# PROC099A_XDS110_Interface_1B.net
KiCad netlist of a schematic drawn in Altium Designer
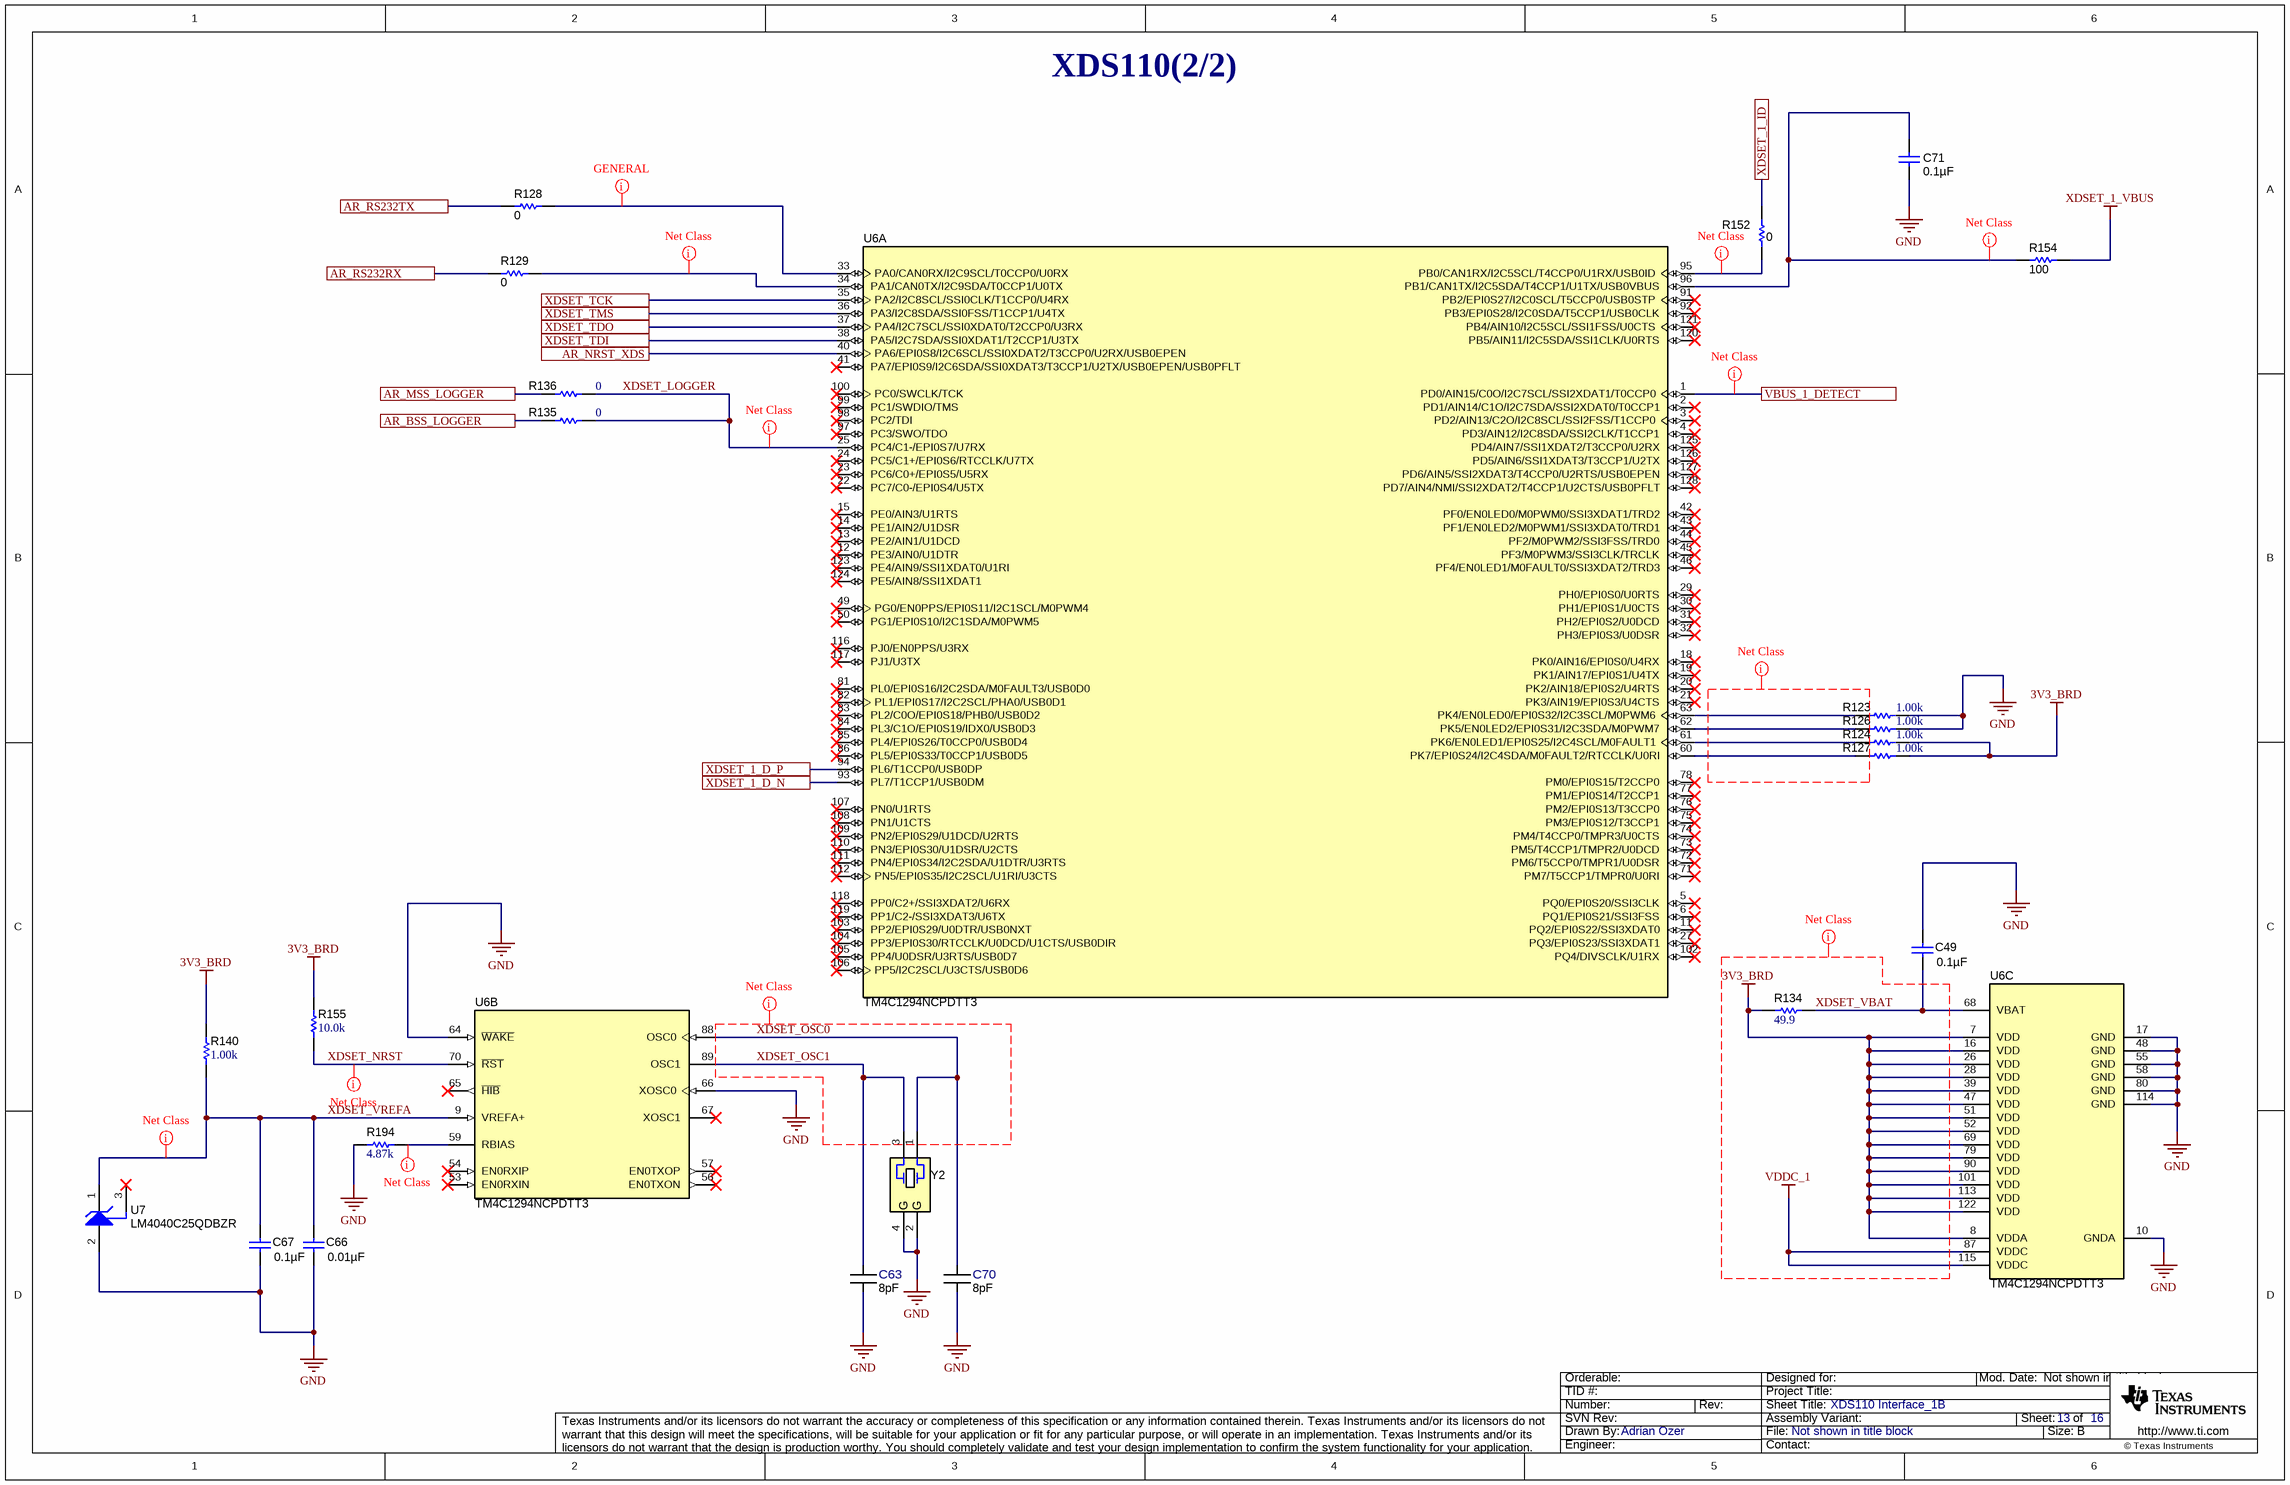
[diagram p0: PROC099A_XDS110 Interface_1B.SchDoc]

(export (version "E")
  (design (tool "Eeschema 10.0.6"))
  (components
    (comp (ref "C49")
      (value "C0402C104K8RACTU")
      (footprint "0402L")
      (description "CAP, CERM, 0.1 µF, 10 V,+/- 10%, X7R, 0402")
      (fields (field (name "MANUFACTURER") "Kemet") (field (name "VALUEDISPLAYED") "0.1µF"))
      (libsource (lib "Altium Vault - TI") (part "CMP-0078241-1"))
    )
    (comp (ref "C63")
      (value "GCM1555C1H8R0DA16D")
      (footprint "FP-GCM1555C1H8R0DA16_0402-MFG")
      (description "Cap Ceramic 8pF 50V C0G 0.5pF SMD 0402 125C Paper T/R")
      (fields (field (name "CAP_F") "8pF") (field (name "MANUFACTURER") "Murata Electronics North America"))
      (libsource (lib "Altium Vault - TI") (part "SYM-B32642B0223J"))
    )
    (comp (ref "C66")
      (value "C0402C103K4RACTU")
      (footprint "0402L")
      (description "CAP, CERM, 0.01 µF, 16 V,+/- 10%, X7R, 0402")
      (fields (field (name "MANUFACTURER") "Kemet") (field (name "VALUEDISPLAYED") "0.01µF"))
      (libsource (lib "Altium Vault - TI") (part "Capacitor"))
    )
    (comp (ref "C67")
      (value "C0402C104K8RACTU")
      (footprint "0402L")
      (description "CAP, CERM, 0.1 µF, 10 V,+/- 10%, X7R, 0402")
      (fields (field (name "MANUFACTURER") "Kemet") (field (name "VALUEDISPLAYED") "0.1µF"))
      (libsource (lib "Altium Vault - TI") (part "Capacitor"))
    )
    (comp (ref "C70")
      (value "GCM1555C1H8R0DA16D")
      (footprint "FP-GCM1555C1H8R0DA16_0402-MFG")
      (description "Cap Ceramic 8pF 50V C0G 0.5pF SMD 0402 125C Paper T/R")
      (fields (field (name "CAP_F") "8pF") (field (name "MANUFACTURER") "Murata Electronics North America"))
      (libsource (lib "Altium Vault - TI") (part "SYM-B32642B0223J"))
    )
    (comp (ref "C71")
      (value "C0402C104K8RACTU")
      (footprint "0402L")
      (description "CAP, CERM, 0.1 µF, 10 V,+/- 10%, X7R, 0402")
      (fields (field (name "MANUFACTURER") "Kemet") (field (name "VALUEDISPLAYED") "0.1µF"))
      (libsource (lib "Altium Vault - TI") (part "Capacitor"))
    )
    (comp (ref "R123")
      (value "CRCW04021K00FKED")
      (footprint "0402L")
      (description "RES, 1.00 k, 1%, 0.063 W, AEC-Q200 Grade 0, 0402")
      (fields (field (name "MANUFACTURER") "Vishay-Dale") (field (name "VALUEDISPLAYED") "1.00k"))
      (libsource (lib "Altium Vault - TI") (part "Resistor"))
    )
    (comp (ref "R124")
      (value "CRCW04021K00FKED")
      (footprint "0402L")
      (description "RES, 1.00 k, 1%, 0.063 W, AEC-Q200 Grade 0, 0402")
      (fields (field (name "MANUFACTURER") "Vishay-Dale") (field (name "VALUEDISPLAYED") "1.00k"))
      (libsource (lib "Altium Vault - TI") (part "Resistor"))
    )
    (comp (ref "R126")
      (value "CRCW04021K00FKED")
      (footprint "0402L")
      (description "RES, 1.00 k, 1%, 0.063 W, AEC-Q200 Grade 0, 0402")
      (fields (field (name "MANUFACTURER") "Vishay-Dale") (field (name "VALUEDISPLAYED") "1.00k"))
      (libsource (lib "Altium Vault - TI") (part "Resistor"))
    )
    (comp (ref "R127")
      (value "CRCW04021K00FKED")
      (footprint "0402L")
      (description "RES, 1.00 k, 1%, 0.063 W, AEC-Q200 Grade 0, 0402")
      (fields (field (name "MANUFACTURER") "Vishay-Dale") (field (name "VALUEDISPLAYED") "1.00k"))
      (libsource (lib "Altium Vault - TI") (part "Resistor"))
    )
    (comp (ref "R128")
      (value "ERJ-2GE0R00X")
      (footprint "0402L")
      (description "RES, 0, 5%, 0.063 W, 0402")
      (fields
        (field (name "MANUFACTURER") "Panasonic")
        (field (name "VALUEDISPLAYED") "0")
        (field (name "PUBLISHER") "Texas Instruments")
      )
      (libsource (lib "Altium Vault - TI") (part "Resistor"))
    )
    (comp (ref "R129")
      (value "ERJ-2GE0R00X")
      (footprint "0402L")
      (description "RES, 0, 5%, 0.063 W, 0402")
      (fields
        (field (name "MANUFACTURER") "Panasonic")
        (field (name "VALUEDISPLAYED") "0")
        (field (name "PUBLISHER") "Texas Instruments")
      )
      (libsource (lib "Altium Vault - TI") (part "Resistor"))
    )
    (comp (ref "R134")
      (value "CRCW040249R9FKED")
      (footprint "0402L")
      (description "RES, 49.9, 1%, 0.063 W, AEC-Q200 Grade 0, 0402")
      (fields (field (name "MANUFACTURER") "Vishay-Dale") (field (name "VALUEDISPLAYED") "49.9"))
      (libsource (lib "Altium Vault - TI") (part "Resistor"))
    )
    (comp (ref "R135")
      (value "CRCW02010000Z0ED")
      (footprint "0201_Silk")
      (description "RES, 0, 5%, 0.05 W, 0201")
      (fields (field (name "MANUFACTURER") "Vishay-Dale") (field (name "VALUEDISPLAYED") "0"))
      (libsource (lib "Altium Vault - TI") (part "Resistor"))
    )
    (comp (ref "R136")
      (value "CRCW02010000Z0ED")
      (footprint "0201_Silk")
      (description "RES, 0, 5%, 0.05 W, 0201")
      (fields (field (name "MANUFACTURER") "Vishay-Dale") (field (name "VALUEDISPLAYED") "0"))
      (libsource (lib "Altium Vault - TI") (part "Resistor"))
    )
    (comp (ref "R140")
      (value "CRCW04021K00FKED")
      (footprint "0402L")
      (description "RES, 1.00 k, 1%, 0.063 W, AEC-Q200 Grade 0, 0402")
      (fields (field (name "MANUFACTURER") "Vishay-Dale") (field (name "VALUEDISPLAYED") "1.00k"))
      (libsource (lib "Altium Vault - TI") (part "Resistor"))
    )
    (comp (ref "R152")
      (value "ERJ-2GE0R00X")
      (footprint "0402L")
      (description "RES, 0, 5%, 0.063 W, 0402")
      (fields
        (field (name "MANUFACTURER") "Panasonic")
        (field (name "VALUEDISPLAYED") "0")
        (field (name "PUBLISHER") "Texas Instruments")
      )
      (libsource (lib "Altium Vault - TI") (part "Resistor"))
    )
    (comp (ref "R154")
      (value "ERJ-2GEJ101X")
      (footprint "0402L")
      (description "RES, 100, 5%, 0.1 W, AEC-Q200 Grade 0, 0402")
      (fields
        (field (name "MANUFACTURER") "Panasonic")
        (field (name "VALUEDISPLAYED") "100")
        (field (name "PUBLISHER") "Texas Instruments")
      )
      (libsource (lib "Altium Vault - TI") (part "Resistor"))
    )
    (comp (ref "R155")
      (value "CRCW040210K0FKED")
      (footprint "0402L")
      (description "RES, 10.0 k, 1%, 0.063 W, AEC-Q200 Grade 0, 0402")
      (fields (field (name "MANUFACTURER") "Vishay-Dale") (field (name "VALUEDISPLAYED") "10.0k"))
      (libsource (lib "Altium Vault - TI") (part "Resistor"))
    )
    (comp (ref "R194")
      (value "CRCW04024K87FKED")
      (footprint "0402L")
      (description "RES, 4.87 k, 1%, 0.063 W, AEC-Q200 Grade 0, 0402")
      (fields (field (name "MANUFACTURER") "Vishay-Dale") (field (name "VALUEDISPLAYED") "4.87k"))
      (libsource (lib "Altium Vault - TI") (part "Resistor"))
    )
    (comp (ref "U6")
      (value "TM4C1294NCPDTT3")
      (footprint "PDT0128A")
      (fields (field (name "PARTNUMBER") "TM4C1294NCPDTT3") (field (name "MANUFACTURER") "Texas Instruments"))
      (libsource (lib "Altium Vault - TI") (part "TI-TM4C1294NCPDT-128"))
    )
    (comp (ref "U7")
      (value "LM4040C25QDBZR")
      (footprint "DBZ0003A_N")
      (fields (field (name "MANUFACTURER") "Texas Instruments") (field (name "PARTNUMBER") "LM4040C25QDBZR"))
      (libsource (lib "Altium Vault - TI") (part "TI-LM4040C25DBZ3"))
    )
    (comp (ref "Y2")
      (value "NX3225SA-16.000M-STD-CRS-2")
      (footprint "NDK_NX3225SA")
      (description "Crystal, 16 MHz, 15 ppm, 8 pF, AEC-Q200 Grade 1, SMD")
      (fields (field (name "MANUFACTURER") "NDK"))
      (libsource (lib "Altium Vault - TI") (part "CMP-0078214-2"))
    )
  )
  (nets
    (net (code "1") (name "/AR_BSS_LOGGER") (class "Default")
      (node (ref "R135") (pin "1") (pinfunction "1_1") (pintype "passive"))
    )
    (net (code "2") (name "/AR_MSS_LOGGER") (class "Default")
      (node (ref "R136") (pin "1") (pinfunction "1_1") (pintype "passive"))
    )
    (net (code "3") (name "/AR_NRST_XDS") (class "Default")
      (node (ref "U6") (pin "40") (pinfunction "PA6/EPI0S8/I2C6SCL/SSI0XDAT2/T3CCP0/U2RX/USB0EPEN_40") (pintype "bidirectional"))
    )
    (net (code "4") (name "/AR_RS232RX") (class "Default")
      (node (ref "R129") (pin "1") (pinfunction "1_1") (pintype "passive"))
    )
    (net (code "5") (name "/AR_RS232TX") (class "Default")
      (node (ref "R128") (pin "1") (pinfunction "1_1") (pintype "passive"))
    )
    (net (code "6") (name "/VBUS_1_DETECT") (class "Default")
      (node (ref "U6") (pin "1") (pinfunction "PD0/AIN15/C0O/I2C7SCL/SSI2XDAT1/T0CCP0_1") (pintype "bidirectional"))
    )
    (net (code "7") (name "/XDSET_1_D_N") (class "Default")
      (node (ref "U6") (pin "93") (pinfunction "PL7/T1CCP1/USB0DM_93") (pintype "bidirectional"))
    )
    (net (code "8") (name "/XDSET_1_D_P") (class "Default")
      (node (ref "U6") (pin "94") (pinfunction "PL6/T1CCP0/USB0DP_94") (pintype "bidirectional"))
    )
    (net (code "9") (name "/XDSET_1_ID") (class "Default")
      (node (ref "R152") (pin "2") (pinfunction "2_2") (pintype "passive"))
    )
    (net (code "10") (name "/XDSET_LOGGER") (class "Default")
      (node (ref "R135") (pin "2") (pinfunction "2_2") (pintype "passive"))
      (node (ref "R136") (pin "2") (pinfunction "2_2") (pintype "passive"))
      (node (ref "U6") (pin "25") (pinfunction "PC4/C1-/EPI0S7/U7RX_25") (pintype "bidirectional"))
    )
    (net (code "11") (name "/XDSET_NRST") (class "Default")
      (node (ref "R155") (pin "1") (pinfunction "1_1") (pintype "passive"))
      (node (ref "U6") (pin "70") (pinfunction "~{RST}_70") (pintype "input"))
    )
    (net (code "12") (name "/XDSET_OSC0") (class "Default")
      (node (ref "C70") (pin "1") (pinfunction "1_1") (pintype "passive"))
      (node (ref "U6") (pin "88") (pinfunction "OSC0_88") (pintype "input"))
      (node (ref "Y2") (pin "1") (pinfunction "1_1") (pintype "passive"))
    )
    (net (code "13") (name "/XDSET_OSC1") (class "Default")
      (node (ref "C63") (pin "1") (pinfunction "1_1") (pintype "passive"))
      (node (ref "U6") (pin "89") (pinfunction "OSC1_89") (pintype "passive"))
      (node (ref "Y2") (pin "3") (pinfunction "3_3") (pintype "passive"))
    )
    (net (code "14") (name "/XDSET_TCK") (class "Default")
      (node (ref "U6") (pin "35") (pinfunction "PA2/I2C8SCL/SSI0CLK/T1CCP0/U4RX_35") (pintype "bidirectional"))
    )
    (net (code "15") (name "/XDSET_TDI") (class "Default")
      (node (ref "U6") (pin "38") (pinfunction "PA5/I2C7SDA/SSI0XDAT1/T2CCP1/U3TX_38") (pintype "bidirectional"))
    )
    (net (code "16") (name "/XDSET_TDO") (class "Default")
      (node (ref "U6") (pin "37") (pinfunction "PA4/I2C7SCL/SSI0XDAT0/T2CCP0/U3RX_37") (pintype "bidirectional"))
    )
    (net (code "17") (name "/XDSET_TMS") (class "Default")
      (node (ref "U6") (pin "36") (pinfunction "PA3/I2C8SDA/SSI0FSS/T1CCP1/U4TX_36") (pintype "bidirectional"))
    )
    (net (code "18") (name "/XDSET_VBAT") (class "Default")
      (node (ref "C49") (pin "2") (pinfunction "2_2") (pintype "passive"))
      (node (ref "R134") (pin "1") (pinfunction "1_1") (pintype "passive"))
      (node (ref "U6") (pin "68") (pinfunction "VBAT_68") (pintype "power_in"))
    )
    (net (code "19") (name "/XDSET_VREFA") (class "Default")
      (node (ref "C66") (pin "2") (pinfunction "2_2") (pintype "passive"))
      (node (ref "C67") (pin "2") (pinfunction "2_2") (pintype "passive"))
      (node (ref "R140") (pin "1") (pinfunction "1_1") (pintype "passive"))
      (node (ref "U6") (pin "9") (pinfunction "VREFA+_9") (pintype "input"))
      (node (ref "U7") (pin "1") (pinfunction "CATHODE_1") (pintype "passive"))
    )
    (net (code "20") (name "3V3_BRD") (class "Default")
      (node (ref "R124") (pin "2") (pinfunction "2_2") (pintype "passive"))
      (node (ref "R127") (pin "2") (pinfunction "2_2") (pintype "passive"))
      (node (ref "R134") (pin "2") (pinfunction "2_2") (pintype "passive"))
      (node (ref "R140") (pin "2") (pinfunction "2_2") (pintype "passive"))
      (node (ref "R155") (pin "2") (pinfunction "2_2") (pintype "passive"))
      (node (ref "U6") (pin "101") (pinfunction "VDD_101") (pintype "power_in"))
      (node (ref "U6") (pin "113") (pinfunction "VDD_113") (pintype "power_in"))
      (node (ref "U6") (pin "122") (pinfunction "VDD_122") (pintype "power_in"))
      (node (ref "U6") (pin "16") (pinfunction "VDD_16") (pintype "power_in"))
      (node (ref "U6") (pin "26") (pinfunction "VDD_26") (pintype "power_in"))
      (node (ref "U6") (pin "28") (pinfunction "VDD_28") (pintype "power_in"))
      (node (ref "U6") (pin "39") (pinfunction "VDD_39") (pintype "power_in"))
      (node (ref "U6") (pin "47") (pinfunction "VDD_47") (pintype "power_in"))
      (node (ref "U6") (pin "51") (pinfunction "VDD_51") (pintype "power_in"))
      (node (ref "U6") (pin "52") (pinfunction "VDD_52") (pintype "power_in"))
      (node (ref "U6") (pin "69") (pinfunction "VDD_69") (pintype "power_in"))
      (node (ref "U6") (pin "7") (pinfunction "VDD_7") (pintype "power_in"))
      (node (ref "U6") (pin "79") (pinfunction "VDD_79") (pintype "power_in"))
      (node (ref "U6") (pin "8") (pinfunction "VDDA_8") (pintype "power_in"))
      (node (ref "U6") (pin "90") (pinfunction "VDD_90") (pintype "power_in"))
    )
    (net (code "21") (name "GND") (class "Default")
      (node (ref "C49") (pin "1") (pinfunction "1_1") (pintype "passive"))
      (node (ref "C63") (pin "2") (pinfunction "2_2") (pintype "passive"))
      (node (ref "C66") (pin "1") (pinfunction "1_1") (pintype "passive"))
      (node (ref "C67") (pin "1") (pinfunction "1_1") (pintype "passive"))
      (node (ref "C70") (pin "2") (pinfunction "2_2") (pintype "passive"))
      (node (ref "C71") (pin "1") (pinfunction "1_1") (pintype "passive"))
      (node (ref "R123") (pin "2") (pinfunction "2_2") (pintype "passive"))
      (node (ref "R126") (pin "2") (pinfunction "2_2") (pintype "passive"))
      (node (ref "R194") (pin "1") (pinfunction "1_1") (pintype "passive"))
      (node (ref "U6") (pin "10") (pinfunction "GNDA_10") (pintype "power_in"))
      (node (ref "U6") (pin "114") (pinfunction "GND_114") (pintype "power_in"))
      (node (ref "U6") (pin "17") (pinfunction "GND_17") (pintype "power_in"))
      (node (ref "U6") (pin "48") (pinfunction "GND_48") (pintype "power_in"))
      (node (ref "U6") (pin "55") (pinfunction "GND_55") (pintype "power_in"))
      (node (ref "U6") (pin "58") (pinfunction "GND_58") (pintype "power_in"))
      (node (ref "U6") (pin "64") (pinfunction "~{WAKE}_64") (pintype "input"))
      (node (ref "U6") (pin "66") (pinfunction "XOSC0_66") (pintype "input"))
      (node (ref "U6") (pin "80") (pinfunction "GND_80") (pintype "power_in"))
      (node (ref "U7") (pin "2") (pinfunction "ANODE_2") (pintype "passive"))
      (node (ref "Y2") (pin "2") (pinfunction "GND_2") (pintype "power_in"))
      (node (ref "Y2") (pin "4") (pinfunction "GND_4") (pintype "power_in"))
    )
    (net (code "22") (name "Net-(U6A-PA0{slash}CAN0RX{slash}I2C9SCL{slash}T0CCP0{slash}U0RX)") (class "Default")
      (node (ref "R128") (pin "2") (pinfunction "2_2") (pintype "passive"))
      (node (ref "U6") (pin "33") (pinfunction "PA0/CAN0RX/I2C9SCL/T0CCP0/U0RX_33") (pintype "bidirectional"))
    )
    (net (code "23") (name "Net-(U6A-PA1{slash}CAN0TX{slash}I2C9SDA{slash}T0CCP1{slash}U0TX)") (class "Default")
      (node (ref "R129") (pin "2") (pinfunction "2_2") (pintype "passive"))
      (node (ref "U6") (pin "34") (pinfunction "PA1/CAN0TX/I2C9SDA/T0CCP1/U0TX_34") (pintype "bidirectional"))
    )
    (net (code "24") (name "Net-(U6A-PB0{slash}CAN1RX{slash}I2C5SCL{slash}T4CCP0{slash}U1RX{slash}USB0ID)") (class "Default")
      (node (ref "R152") (pin "1") (pinfunction "1_1") (pintype "passive"))
      (node (ref "U6") (pin "95") (pinfunction "PB0/CAN1RX/I2C5SCL/T4CCP0/U1RX/USB0ID_95") (pintype "bidirectional"))
    )
    (net (code "25") (name "Net-(U6A-PB1{slash}CAN1TX{slash}I2C5SDA{slash}T4CCP1{slash}U1TX{slash}USB0VBUS)") (class "Default")
      (node (ref "C71") (pin "2") (pinfunction "2_2") (pintype "passive"))
      (node (ref "R154") (pin "1") (pinfunction "1_1") (pintype "passive"))
      (node (ref "U6") (pin "96") (pinfunction "PB1/CAN1TX/I2C5SDA/T4CCP1/U1TX/USB0VBUS_96") (pintype "bidirectional"))
    )
    (net (code "26") (name "Net-(U6A-PK4{slash}EN0LED0{slash}EPI0S32{slash}I2C3SCL{slash}M0PWM6)") (class "Default")
      (node (ref "R123") (pin "1") (pinfunction "1_1") (pintype "passive"))
      (node (ref "U6") (pin "63") (pinfunction "PK4/EN0LED0/EPI0S32/I2C3SCL/M0PWM6_63") (pintype "bidirectional"))
    )
    (net (code "27") (name "Net-(U6A-PK5{slash}EN0LED2{slash}EPI0S31{slash}I2C3SDA{slash}M0PWM7)") (class "Default")
      (node (ref "R126") (pin "1") (pinfunction "1_1") (pintype "passive"))
      (node (ref "U6") (pin "62") (pinfunction "PK5/EN0LED2/EPI0S31/I2C3SDA/M0PWM7_62") (pintype "bidirectional"))
    )
    (net (code "28") (name "Net-(U6A-PK6{slash}EN0LED1{slash}EPI0S25{slash}I2C4SCL{slash}M0FAULT1)") (class "Default")
      (node (ref "R124") (pin "1") (pinfunction "1_1") (pintype "passive"))
      (node (ref "U6") (pin "61") (pinfunction "PK6/EN0LED1/EPI0S25/I2C4SCL/M0FAULT1_61") (pintype "bidirectional"))
    )
    (net (code "29") (name "Net-(U6A-PK7{slash}EPI0S24{slash}I2C4SDA{slash}M0FAULT2{slash}RTCCLK{slash}U0RI)") (class "Default")
      (node (ref "R127") (pin "1") (pinfunction "1_1") (pintype "passive"))
      (node (ref "U6") (pin "60") (pinfunction "PK7/EPI0S24/I2C4SDA/M0FAULT2/RTCCLK/U0RI_60") (pintype "bidirectional"))
    )
    (net (code "30") (name "Net-(U6B-RBIAS)") (class "Default")
      (node (ref "R194") (pin "2") (pinfunction "2_2") (pintype "passive"))
      (node (ref "U6") (pin "59") (pinfunction "RBIAS_59") (pintype "passive"))
    )
    (net (code "31") (name "VDDC_1") (class "Default")
      (node (ref "U6") (pin "115") (pinfunction "VDDC_115") (pintype "power_in"))
      (node (ref "U6") (pin "87") (pinfunction "VDDC_87") (pintype "power_in"))
    )
    (net (code "32") (name "XDSET_1_VBUS") (class "Default")
      (node (ref "R154") (pin "2") (pinfunction "2_2") (pintype "passive"))
    )
    (net (code "33") (name "unconnected-(U6A-PA7{slash}EPI0S9{slash}I2C6SDA{slash}SSI0XDAT3{slash}T3CCP1{slash}U2TX{slash}USB0EPEN{slash}USB0PFLT-Pad41)") (class "Default")
      (node (ref "U6") (pin "41") (pinfunction "PA7/EPI0S9/I2C6SDA/SSI0XDAT3/T3CCP1/U2TX/USB0EPEN/USB0PFLT_41") (pintype "bidirectional+no_connect"))
    )
    (net (code "34") (name "unconnected-(U6A-PB2{slash}EPI0S27{slash}I2C0SCL{slash}T5CCP0{slash}USB0STP-Pad91)") (class "Default")
      (node (ref "U6") (pin "91") (pinfunction "PB2/EPI0S27/I2C0SCL/T5CCP0/USB0STP_91") (pintype "bidirectional+no_connect"))
    )
    (net (code "35") (name "unconnected-(U6A-PB3{slash}EPI0S28{slash}I2C0SDA{slash}T5CCP1{slash}USB0CLK-Pad92)") (class "Default")
      (node (ref "U6") (pin "92") (pinfunction "PB3/EPI0S28/I2C0SDA/T5CCP1/USB0CLK_92") (pintype "bidirectional+no_connect"))
    )
    (net (code "36") (name "unconnected-(U6A-PB4{slash}AIN10{slash}I2C5SCL{slash}SSI1FSS{slash}U0CTS-Pad121)") (class "Default")
      (node (ref "U6") (pin "121") (pinfunction "PB4/AIN10/I2C5SCL/SSI1FSS/U0CTS_121") (pintype "bidirectional+no_connect"))
    )
    (net (code "37") (name "unconnected-(U6A-PB5{slash}AIN11{slash}I2C5SDA{slash}SSI1CLK{slash}U0RTS-Pad120)") (class "Default")
      (node (ref "U6") (pin "120") (pinfunction "PB5/AIN11/I2C5SDA/SSI1CLK/U0RTS_120") (pintype "bidirectional+no_connect"))
    )
    (net (code "38") (name "unconnected-(U6A-PC0{slash}SWCLK{slash}TCK-Pad100)") (class "Default")
      (node (ref "U6") (pin "100") (pinfunction "PC0/SWCLK/TCK_100") (pintype "bidirectional+no_connect"))
    )
    (net (code "39") (name "unconnected-(U6A-PC1{slash}SWDIO{slash}TMS-Pad99)") (class "Default")
      (node (ref "U6") (pin "99") (pinfunction "PC1/SWDIO/TMS_99") (pintype "bidirectional+no_connect"))
    )
    (net (code "40") (name "unconnected-(U6A-PC2{slash}TDI-Pad98)") (class "Default")
      (node (ref "U6") (pin "98") (pinfunction "PC2/TDI_98") (pintype "bidirectional+no_connect"))
    )
    (net (code "41") (name "unconnected-(U6A-PC3{slash}SWO{slash}TDO-Pad97)") (class "Default")
      (node (ref "U6") (pin "97") (pinfunction "PC3/SWO/TDO_97") (pintype "bidirectional+no_connect"))
    )
    (net (code "42") (name "unconnected-(U6A-PC5{slash}C1+{slash}EPI0S6{slash}RTCCLK{slash}U7TX-Pad24)") (class "Default")
      (node (ref "U6") (pin "24") (pinfunction "PC5/C1+/EPI0S6/RTCCLK/U7TX_24") (pintype "bidirectional+no_connect"))
    )
    (net (code "43") (name "unconnected-(U6A-PC6{slash}C0+{slash}EPI0S5{slash}U5RX-Pad23)") (class "Default")
      (node (ref "U6") (pin "23") (pinfunction "PC6/C0+/EPI0S5/U5RX_23") (pintype "bidirectional+no_connect"))
    )
    (net (code "44") (name "unconnected-(U6A-PC7{slash}C0-{slash}EPI0S4{slash}U5TX-Pad22)") (class "Default")
      (node (ref "U6") (pin "22") (pinfunction "PC7/C0-/EPI0S4/U5TX_22") (pintype "bidirectional+no_connect"))
    )
    (net (code "45") (name "unconnected-(U6A-PD1{slash}AIN14{slash}C1O{slash}I2C7SDA{slash}SSI2XDAT0{slash}T0CCP1-Pad2)") (class "Default")
      (node (ref "U6") (pin "2") (pinfunction "PD1/AIN14/C1O/I2C7SDA/SSI2XDAT0/T0CCP1_2") (pintype "bidirectional+no_connect"))
    )
    (net (code "46") (name "unconnected-(U6A-PD2{slash}AIN13{slash}C2O{slash}I2C8SCL{slash}SSI2FSS{slash}T1CCP0-Pad3)") (class "Default")
      (node (ref "U6") (pin "3") (pinfunction "PD2/AIN13/C2O/I2C8SCL/SSI2FSS/T1CCP0_3") (pintype "bidirectional+no_connect"))
    )
    (net (code "47") (name "unconnected-(U6A-PD3{slash}AIN12{slash}I2C8SDA{slash}SSI2CLK{slash}T1CCP1-Pad4)") (class "Default")
      (node (ref "U6") (pin "4") (pinfunction "PD3/AIN12/I2C8SDA/SSI2CLK/T1CCP1_4") (pintype "bidirectional+no_connect"))
    )
    (net (code "48") (name "unconnected-(U6A-PD4{slash}AIN7{slash}SSI1XDAT2{slash}T3CCP0{slash}U2RX-Pad125)") (class "Default")
      (node (ref "U6") (pin "125") (pinfunction "PD4/AIN7/SSI1XDAT2/T3CCP0/U2RX_125") (pintype "bidirectional+no_connect"))
    )
    (net (code "49") (name "unconnected-(U6A-PD5{slash}AIN6{slash}SSI1XDAT3{slash}T3CCP1{slash}U2TX-Pad126)") (class "Default")
      (node (ref "U6") (pin "126") (pinfunction "PD5/AIN6/SSI1XDAT3/T3CCP1/U2TX_126") (pintype "bidirectional+no_connect"))
    )
    (net (code "50") (name "unconnected-(U6A-PD6{slash}AIN5{slash}SSI2XDAT3{slash}T4CCP0{slash}U2RTS{slash}USB0EPEN-Pad127)") (class "Default")
      (node (ref "U6") (pin "127") (pinfunction "PD6/AIN5/SSI2XDAT3/T4CCP0/U2RTS/USB0EPEN_127") (pintype "bidirectional+no_connect"))
    )
    (net (code "51") (name "unconnected-(U6A-PD7{slash}AIN4{slash}NMI{slash}SSI2XDAT2{slash}T4CCP1{slash}U2CTS{slash}USB0PFLT-Pad128)") (class "Default")
      (node (ref "U6") (pin "128") (pinfunction "PD7/AIN4/NMI/SSI2XDAT2/T4CCP1/U2CTS/USB0PFLT_128") (pintype "bidirectional+no_connect"))
    )
    (net (code "52") (name "unconnected-(U6A-PE0{slash}AIN3{slash}U1RTS-Pad15)") (class "Default")
      (node (ref "U6") (pin "15") (pinfunction "PE0/AIN3/U1RTS_15") (pintype "bidirectional+no_connect"))
    )
    (net (code "53") (name "unconnected-(U6A-PE1{slash}AIN2{slash}U1DSR-Pad14)") (class "Default")
      (node (ref "U6") (pin "14") (pinfunction "PE1/AIN2/U1DSR_14") (pintype "bidirectional+no_connect"))
    )
    (net (code "54") (name "unconnected-(U6A-PE2{slash}AIN1{slash}U1DCD-Pad13)") (class "Default")
      (node (ref "U6") (pin "13") (pinfunction "PE2/AIN1/U1DCD_13") (pintype "bidirectional+no_connect"))
    )
    (net (code "55") (name "unconnected-(U6A-PE3{slash}AIN0{slash}U1DTR-Pad12)") (class "Default")
      (node (ref "U6") (pin "12") (pinfunction "PE3/AIN0/U1DTR_12") (pintype "bidirectional+no_connect"))
    )
    (net (code "56") (name "unconnected-(U6A-PE4{slash}AIN9{slash}SSI1XDAT0{slash}U1RI-Pad123)") (class "Default")
      (node (ref "U6") (pin "123") (pinfunction "PE4/AIN9/SSI1XDAT0/U1RI_123") (pintype "bidirectional+no_connect"))
    )
    (net (code "57") (name "unconnected-(U6A-PE5{slash}AIN8{slash}SSI1XDAT1-Pad124)") (class "Default")
      (node (ref "U6") (pin "124") (pinfunction "PE5/AIN8/SSI1XDAT1_124") (pintype "bidirectional+no_connect"))
    )
    (net (code "58") (name "unconnected-(U6A-PF0{slash}EN0LED0{slash}M0PWM0{slash}SSI3XDAT1{slash}TRD2-Pad42)") (class "Default")
      (node (ref "U6") (pin "42") (pinfunction "PF0/EN0LED0/M0PWM0/SSI3XDAT1/TRD2_42") (pintype "bidirectional+no_connect"))
    )
    (net (code "59") (name "unconnected-(U6A-PF1{slash}EN0LED2{slash}M0PWM1{slash}SSI3XDAT0{slash}TRD1-Pad43)") (class "Default")
      (node (ref "U6") (pin "43") (pinfunction "PF1/EN0LED2/M0PWM1/SSI3XDAT0/TRD1_43") (pintype "bidirectional+no_connect"))
    )
    (net (code "60") (name "unconnected-(U6A-PF2{slash}M0PWM2{slash}SSI3FSS{slash}TRD0-Pad44)") (class "Default")
      (node (ref "U6") (pin "44") (pinfunction "PF2/M0PWM2/SSI3FSS/TRD0_44") (pintype "bidirectional+no_connect"))
    )
    (net (code "61") (name "unconnected-(U6A-PF3{slash}M0PWM3{slash}SSI3CLK{slash}TRCLK-Pad45)") (class "Default")
      (node (ref "U6") (pin "45") (pinfunction "PF3/M0PWM3/SSI3CLK/TRCLK_45") (pintype "bidirectional+no_connect"))
    )
    (net (code "62") (name "unconnected-(U6A-PF4{slash}EN0LED1{slash}M0FAULT0{slash}SSI3XDAT2{slash}TRD3-Pad46)") (class "Default")
      (node (ref "U6") (pin "46") (pinfunction "PF4/EN0LED1/M0FAULT0/SSI3XDAT2/TRD3_46") (pintype "bidirectional+no_connect"))
    )
    (net (code "63") (name "unconnected-(U6A-PG0{slash}EN0PPS{slash}EPI0S11{slash}I2C1SCL{slash}M0PWM4-Pad49)") (class "Default")
      (node (ref "U6") (pin "49") (pinfunction "PG0/EN0PPS/EPI0S11/I2C1SCL/M0PWM4_49") (pintype "bidirectional+no_connect"))
    )
    (net (code "64") (name "unconnected-(U6A-PG1{slash}EPI0S10{slash}I2C1SDA{slash}M0PWM5-Pad50)") (class "Default")
      (node (ref "U6") (pin "50") (pinfunction "PG1/EPI0S10/I2C1SDA/M0PWM5_50") (pintype "bidirectional+no_connect"))
    )
    (net (code "65") (name "unconnected-(U6A-PH0{slash}EPI0S0{slash}U0RTS-Pad29)") (class "Default")
      (node (ref "U6") (pin "29") (pinfunction "PH0/EPI0S0/U0RTS_29") (pintype "bidirectional+no_connect"))
    )
    (net (code "66") (name "unconnected-(U6A-PH1{slash}EPI0S1{slash}U0CTS-Pad30)") (class "Default")
      (node (ref "U6") (pin "30") (pinfunction "PH1/EPI0S1/U0CTS_30") (pintype "bidirectional+no_connect"))
    )
    (net (code "67") (name "unconnected-(U6A-PH2{slash}EPI0S2{slash}U0DCD-Pad31)") (class "Default")
      (node (ref "U6") (pin "31") (pinfunction "PH2/EPI0S2/U0DCD_31") (pintype "bidirectional+no_connect"))
    )
    (net (code "68") (name "unconnected-(U6A-PH3{slash}EPI0S3{slash}U0DSR-Pad32)") (class "Default")
      (node (ref "U6") (pin "32") (pinfunction "PH3/EPI0S3/U0DSR_32") (pintype "bidirectional+no_connect"))
    )
    (net (code "69") (name "unconnected-(U6A-PJ0{slash}EN0PPS{slash}U3RX-Pad116)") (class "Default")
      (node (ref "U6") (pin "116") (pinfunction "PJ0/EN0PPS/U3RX_116") (pintype "bidirectional+no_connect"))
    )
    (net (code "70") (name "unconnected-(U6A-PJ1{slash}U3TX-Pad117)") (class "Default")
      (node (ref "U6") (pin "117") (pinfunction "PJ1/U3TX_117") (pintype "bidirectional+no_connect"))
    )
    (net (code "71") (name "unconnected-(U6A-PK0{slash}AIN16{slash}EPI0S0{slash}U4RX-Pad18)") (class "Default")
      (node (ref "U6") (pin "18") (pinfunction "PK0/AIN16/EPI0S0/U4RX_18") (pintype "bidirectional+no_connect"))
    )
    (net (code "72") (name "unconnected-(U6A-PK1{slash}AIN17{slash}EPI0S1{slash}U4TX-Pad19)") (class "Default")
      (node (ref "U6") (pin "19") (pinfunction "PK1/AIN17/EPI0S1/U4TX_19") (pintype "bidirectional+no_connect"))
    )
    (net (code "73") (name "unconnected-(U6A-PK2{slash}AIN18{slash}EPI0S2{slash}U4RTS-Pad20)") (class "Default")
      (node (ref "U6") (pin "20") (pinfunction "PK2/AIN18/EPI0S2/U4RTS_20") (pintype "bidirectional+no_connect"))
    )
    (net (code "74") (name "unconnected-(U6A-PK3{slash}AIN19{slash}EPI0S3{slash}U4CTS-Pad21)") (class "Default")
      (node (ref "U6") (pin "21") (pinfunction "PK3/AIN19/EPI0S3/U4CTS_21") (pintype "bidirectional+no_connect"))
    )
    (net (code "75") (name "unconnected-(U6A-PL0{slash}EPI0S16{slash}I2C2SDA{slash}M0FAULT3{slash}USB0D0-Pad81)") (class "Default")
      (node (ref "U6") (pin "81") (pinfunction "PL0/EPI0S16/I2C2SDA/M0FAULT3/USB0D0_81") (pintype "bidirectional+no_connect"))
    )
    (net (code "76") (name "unconnected-(U6A-PL1{slash}EPI0S17{slash}I2C2SCL{slash}PHA0{slash}USB0D1-Pad82)") (class "Default")
      (node (ref "U6") (pin "82") (pinfunction "PL1/EPI0S17/I2C2SCL/PHA0/USB0D1_82") (pintype "bidirectional+no_connect"))
    )
    (net (code "77") (name "unconnected-(U6A-PL2{slash}C0O{slash}EPI0S18{slash}PHB0{slash}USB0D2-Pad83)") (class "Default")
      (node (ref "U6") (pin "83") (pinfunction "PL2/C0O/EPI0S18/PHB0/USB0D2_83") (pintype "bidirectional+no_connect"))
    )
    (net (code "78") (name "unconnected-(U6A-PL3{slash}C1O{slash}EPI0S19{slash}IDX0{slash}USB0D3-Pad84)") (class "Default")
      (node (ref "U6") (pin "84") (pinfunction "PL3/C1O/EPI0S19/IDX0/USB0D3_84") (pintype "bidirectional+no_connect"))
    )
    (net (code "79") (name "unconnected-(U6A-PL4{slash}EPI0S26{slash}T0CCP0{slash}USB0D4-Pad85)") (class "Default")
      (node (ref "U6") (pin "85") (pinfunction "PL4/EPI0S26/T0CCP0/USB0D4_85") (pintype "bidirectional+no_connect"))
    )
    (net (code "80") (name "unconnected-(U6A-PL5{slash}EPI0S33{slash}T0CCP1{slash}USB0D5-Pad86)") (class "Default")
      (node (ref "U6") (pin "86") (pinfunction "PL5/EPI0S33/T0CCP1/USB0D5_86") (pintype "bidirectional+no_connect"))
    )
    (net (code "81") (name "unconnected-(U6A-PM0{slash}EPI0S15{slash}T2CCP0-Pad78)") (class "Default")
      (node (ref "U6") (pin "78") (pinfunction "PM0/EPI0S15/T2CCP0_78") (pintype "bidirectional+no_connect"))
    )
    (net (code "82") (name "unconnected-(U6A-PM1{slash}EPI0S14{slash}T2CCP1-Pad77)") (class "Default")
      (node (ref "U6") (pin "77") (pinfunction "PM1/EPI0S14/T2CCP1_77") (pintype "bidirectional+no_connect"))
    )
    (net (code "83") (name "unconnected-(U6A-PM2{slash}EPI0S13{slash}T3CCP0-Pad76)") (class "Default")
      (node (ref "U6") (pin "76") (pinfunction "PM2/EPI0S13/T3CCP0_76") (pintype "bidirectional+no_connect"))
    )
    (net (code "84") (name "unconnected-(U6A-PM3{slash}EPI0S12{slash}T3CCP1-Pad75)") (class "Default")
      (node (ref "U6") (pin "75") (pinfunction "PM3/EPI0S12/T3CCP1_75") (pintype "bidirectional+no_connect"))
    )
    (net (code "85") (name "unconnected-(U6A-PM4{slash}T4CCP0{slash}TMPR3{slash}U0CTS-Pad74)") (class "Default")
      (node (ref "U6") (pin "74") (pinfunction "PM4/T4CCP0/TMPR3/U0CTS_74") (pintype "bidirectional+no_connect"))
    )
    (net (code "86") (name "unconnected-(U6A-PM5{slash}T4CCP1{slash}TMPR2{slash}U0DCD-Pad73)") (class "Default")
      (node (ref "U6") (pin "73") (pinfunction "PM5/T4CCP1/TMPR2/U0DCD_73") (pintype "bidirectional+no_connect"))
    )
    (net (code "87") (name "unconnected-(U6A-PM6{slash}T5CCP0{slash}TMPR1{slash}U0DSR-Pad72)") (class "Default")
      (node (ref "U6") (pin "72") (pinfunction "PM6/T5CCP0/TMPR1/U0DSR_72") (pintype "bidirectional+no_connect"))
    )
    (net (code "88") (name "unconnected-(U6A-PM7{slash}T5CCP1{slash}TMPR0{slash}U0RI-Pad71)") (class "Default")
      (node (ref "U6") (pin "71") (pinfunction "PM7/T5CCP1/TMPR0/U0RI_71") (pintype "bidirectional+no_connect"))
    )
    (net (code "89") (name "unconnected-(U6A-PN0{slash}U1RTS-Pad107)") (class "Default")
      (node (ref "U6") (pin "107") (pinfunction "PN0/U1RTS_107") (pintype "bidirectional+no_connect"))
    )
    (net (code "90") (name "unconnected-(U6A-PN1{slash}U1CTS-Pad108)") (class "Default")
      (node (ref "U6") (pin "108") (pinfunction "PN1/U1CTS_108") (pintype "bidirectional+no_connect"))
    )
    (net (code "91") (name "unconnected-(U6A-PN2{slash}EPI0S29{slash}U1DCD{slash}U2RTS-Pad109)") (class "Default")
      (node (ref "U6") (pin "109") (pinfunction "PN2/EPI0S29/U1DCD/U2RTS_109") (pintype "bidirectional+no_connect"))
    )
    (net (code "92") (name "unconnected-(U6A-PN3{slash}EPI0S30{slash}U1DSR{slash}U2CTS-Pad110)") (class "Default")
      (node (ref "U6") (pin "110") (pinfunction "PN3/EPI0S30/U1DSR/U2CTS_110") (pintype "bidirectional+no_connect"))
    )
    (net (code "93") (name "unconnected-(U6A-PN4{slash}EPI0S34{slash}I2C2SDA{slash}U1DTR{slash}U3RTS-Pad111)") (class "Default")
      (node (ref "U6") (pin "111") (pinfunction "PN4/EPI0S34/I2C2SDA/U1DTR/U3RTS_111") (pintype "bidirectional+no_connect"))
    )
    (net (code "94") (name "unconnected-(U6A-PN5{slash}EPI0S35{slash}I2C2SCL{slash}U1RI{slash}U3CTS-Pad112)") (class "Default")
      (node (ref "U6") (pin "112") (pinfunction "PN5/EPI0S35/I2C2SCL/U1RI/U3CTS_112") (pintype "bidirectional+no_connect"))
    )
    (net (code "95") (name "unconnected-(U6A-PP0{slash}C2+{slash}SSI3XDAT2{slash}U6RX-Pad118)") (class "Default")
      (node (ref "U6") (pin "118") (pinfunction "PP0/C2+/SSI3XDAT2/U6RX_118") (pintype "bidirectional+no_connect"))
    )
    (net (code "96") (name "unconnected-(U6A-PP1{slash}C2-{slash}SSI3XDAT3{slash}U6TX-Pad119)") (class "Default")
      (node (ref "U6") (pin "119") (pinfunction "PP1/C2-/SSI3XDAT3/U6TX_119") (pintype "bidirectional+no_connect"))
    )
    (net (code "97") (name "unconnected-(U6A-PP2{slash}EPI0S29{slash}U0DTR{slash}USB0NXT-Pad103)") (class "Default")
      (node (ref "U6") (pin "103") (pinfunction "PP2/EPI0S29/U0DTR/USB0NXT_103") (pintype "bidirectional+no_connect"))
    )
    (net (code "98") (name "unconnected-(U6A-PP3{slash}EPI0S30{slash}RTCCLK{slash}U0DCD{slash}U1CTS{slash}USB0DIR-Pad104)") (class "Default")
      (node (ref "U6") (pin "104") (pinfunction "PP3/EPI0S30/RTCCLK/U0DCD/U1CTS/USB0DIR_104") (pintype "bidirectional+no_connect"))
    )
    (net (code "99") (name "unconnected-(U6A-PP4{slash}U0DSR{slash}U3RTS{slash}USB0D7-Pad105)") (class "Default")
      (node (ref "U6") (pin "105") (pinfunction "PP4/U0DSR/U3RTS/USB0D7_105") (pintype "bidirectional+no_connect"))
    )
    (net (code "100") (name "unconnected-(U6A-PP5{slash}I2C2SCL{slash}U3CTS{slash}USB0D6-Pad106)") (class "Default")
      (node (ref "U6") (pin "106") (pinfunction "PP5/I2C2SCL/U3CTS/USB0D6_106") (pintype "bidirectional+no_connect"))
    )
    (net (code "101") (name "unconnected-(U6A-PQ0{slash}EPI0S20{slash}SSI3CLK-Pad5)") (class "Default")
      (node (ref "U6") (pin "5") (pinfunction "PQ0/EPI0S20/SSI3CLK_5") (pintype "bidirectional+no_connect"))
    )
    (net (code "102") (name "unconnected-(U6A-PQ1{slash}EPI0S21{slash}SSI3FSS-Pad6)") (class "Default")
      (node (ref "U6") (pin "6") (pinfunction "PQ1/EPI0S21/SSI3FSS_6") (pintype "bidirectional+no_connect"))
    )
    (net (code "103") (name "unconnected-(U6A-PQ2{slash}EPI0S22{slash}SSI3XDAT0-Pad11)") (class "Default")
      (node (ref "U6") (pin "11") (pinfunction "PQ2/EPI0S22/SSI3XDAT0_11") (pintype "bidirectional+no_connect"))
    )
    (net (code "104") (name "unconnected-(U6A-PQ3{slash}EPI0S23{slash}SSI3XDAT1-Pad27)") (class "Default")
      (node (ref "U6") (pin "27") (pinfunction "PQ3/EPI0S23/SSI3XDAT1_27") (pintype "bidirectional+no_connect"))
    )
    (net (code "105") (name "unconnected-(U6A-PQ4{slash}DIVSCLK{slash}U1RX-Pad102)") (class "Default")
      (node (ref "U6") (pin "102") (pinfunction "PQ4/DIVSCLK/U1RX_102") (pintype "bidirectional+no_connect"))
    )
    (net (code "106") (name "unconnected-(U6B-EN0RXIN-Pad53)") (class "Default")
      (node (ref "U6") (pin "53") (pinfunction "EN0RXIN_53") (pintype "input+no_connect"))
    )
    (net (code "107") (name "unconnected-(U6B-EN0RXIP-Pad54)") (class "Default")
      (node (ref "U6") (pin "54") (pinfunction "EN0RXIP_54") (pintype "input+no_connect"))
    )
    (net (code "108") (name "unconnected-(U6B-EN0TXON-Pad56)") (class "Default")
      (node (ref "U6") (pin "56") (pinfunction "EN0TXON_56") (pintype "output+no_connect"))
    )
    (net (code "109") (name "unconnected-(U6B-EN0TXOP-Pad57)") (class "Default")
      (node (ref "U6") (pin "57") (pinfunction "EN0TXOP_57") (pintype "output+no_connect"))
    )
    (net (code "110") (name "unconnected-(U6B-XOSC1-Pad67)") (class "Default")
      (node (ref "U6") (pin "67") (pinfunction "XOSC1_67") (pintype "passive+no_connect"))
    )
    (net (code "111") (name "unconnected-(U6B-~{HIB}-Pad65)") (class "Default")
      (node (ref "U6") (pin "65") (pinfunction "~{HIB}_65") (pintype "output+no_connect"))
    )
    (net (code "112") (name "unconnected-(U7-NC-Pad3)") (class "Default")
      (node (ref "U7") (pin "3") (pinfunction "NC_3") (pintype "passive+no_connect"))
    )
  )
)
